# External_Memory_Power_Switch.net
KiCad netlist of a schematic drawn in Altium Designer
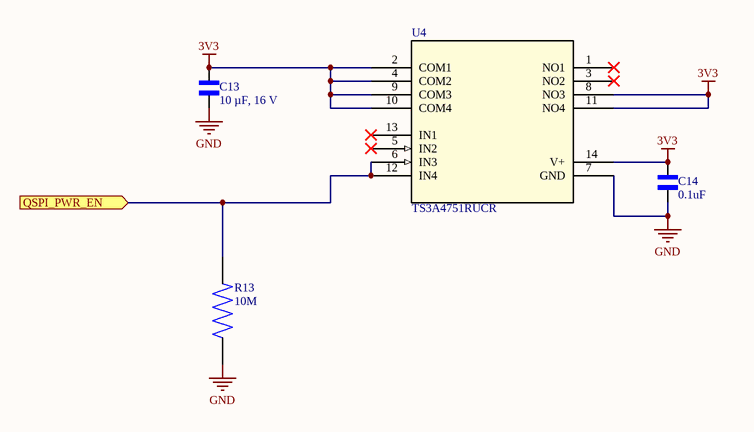
[diagram p0: External_Memory_Power_Switch.SchDoc]

(export (version "E")
  (design (tool "Eeschema 10.0.6"))
  (components
    (comp (ref "C13")
      (value "10 µF, 16 V")
      (footprint "C0805")
      (fields
        (field (name "MANUFACTURER") "TDK")
        (field (name "MANUFACTURER PART NUMBER") "C2012X5R1C106K085AC")
        (field (name "TOLERANCE") "10%")
      )
      (libsource (lib "nnts") (part "C2012X5R1C106K085AC"))
    )
    (comp (ref "C14")
      (value "0.1uF")
      (footprint "C0402")
      (description "CAP CER 0.1UF 6.3V X5R 01005")
      (fields
        (field (name "MANUFACTURER") "Murata")
        (field (name "MANUFACTURER PART NUMBER") "GRM022R60J104KE15L")
      )
      (libsource (lib "nnts") (part "GRM022R60J104KE15L"))
    )
    (comp (ref "R13")
      (value "10M")
      (footprint "R0402 Vishay")
      (fields
        (field (name "MANUFACTURER") "Vishay")
        (field (name "MANUFACTURER PART NUMBER") "CRCW040210M0FKED")
        (field (name "TOLERANCE") "1%")
      )
      (libsource (lib "nnts") (part "CRCW040210M0FKED"))
    )
    (comp (ref "U4")
      (value "TS3A4751RUCR")
      (footprint "TS3A4751RUCR")
      (description "https://www.ti.com/product/TS3A4751?HQS=TI-null-null-octopart-df-pf-null-wwe")
      (fields
        (field (name "GENERIC_PART_NUMBER") "TS3A4751")
        (field (name "MANUFACTURER") "Texas Instruments")
        (field (name "COPYRIGHT") "Copyright (C) 2018 Accelerated Designs. All rights reserved")
      )
      (libsource (lib "nnts") (part "TS3A4751RUCR"))
    )
  )
  (nets
    (net (code "1") (name "/QSPI_PWR_EN") (class "Default")
      (node (ref "R13") (pin "2") (pinfunction "2_2") (pintype "passive"))
      (node (ref "U4") (pin "12") (pinfunction "IN4_12") (pintype "passive"))
      (node (ref "U4") (pin "6") (pinfunction "IN3_6") (pintype "input"))
    )
    (net (code "2") (name "3V3") (class "Default")
      (node (ref "C13") (pin "2") (pinfunction "2_2") (pintype "passive"))
      (node (ref "C14") (pin "2") (pinfunction "2_2") (pintype "passive"))
      (node (ref "U4") (pin "10") (pinfunction "COM4_10") (pintype "passive"))
      (node (ref "U4") (pin "11") (pinfunction "NO4_11") (pintype "passive"))
      (node (ref "U4") (pin "14") (pinfunction "V+_14") (pintype "power_in"))
      (node (ref "U4") (pin "2") (pinfunction "COM1_2") (pintype "passive"))
      (node (ref "U4") (pin "4") (pinfunction "COM2_4") (pintype "passive"))
      (node (ref "U4") (pin "8") (pinfunction "NO3_8") (pintype "passive"))
      (node (ref "U4") (pin "9") (pinfunction "COM3_9") (pintype "passive"))
    )
    (net (code "3") (name "GND") (class "Default")
      (node (ref "C13") (pin "1") (pinfunction "1_1") (pintype "passive"))
      (node (ref "C14") (pin "1") (pinfunction "1_1") (pintype "passive"))
      (node (ref "R13") (pin "1") (pinfunction "1_1") (pintype "passive"))
      (node (ref "U4") (pin "7") (pinfunction "GND_7") (pintype "power_in"))
    )
    (net (code "4") (name "unconnected-(U4-IN1-Pad13)") (class "Default")
      (node (ref "U4") (pin "13") (pinfunction "IN1_13") (pintype "passive+no_connect"))
    )
    (net (code "5") (name "unconnected-(U4-IN2-Pad5)") (class "Default")
      (node (ref "U4") (pin "5") (pinfunction "IN2_5") (pintype "input+no_connect"))
    )
    (net (code "6") (name "unconnected-(U4-NO1-Pad1)") (class "Default")
      (node (ref "U4") (pin "1") (pinfunction "NO1_1") (pintype "passive+no_connect"))
    )
    (net (code "7") (name "unconnected-(U4-NO2-Pad3)") (class "Default")
      (node (ref "U4") (pin "3") (pinfunction "NO2_3") (pintype "passive+no_connect"))
    )
  )
)
